# Uno.net
KiCad netlist of a schematic drawn in EAGLE
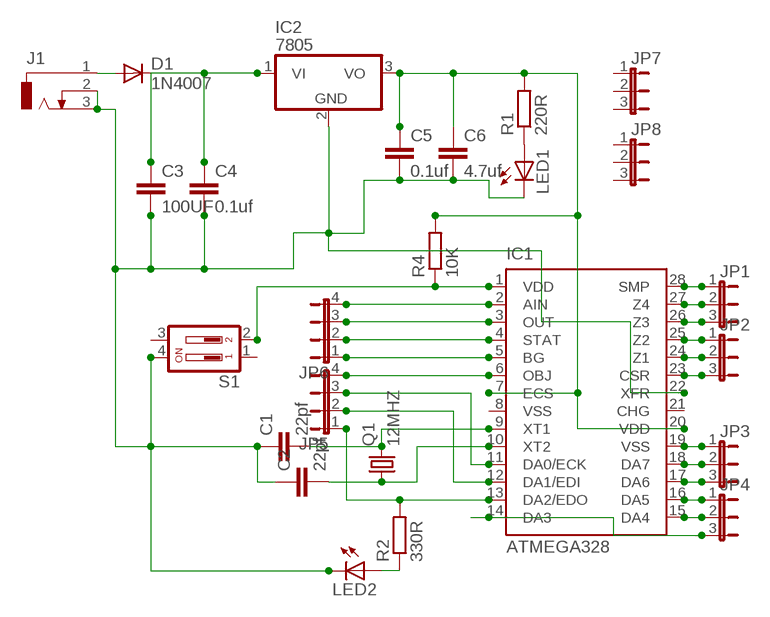
[diagram p0: schematic, sheet 1]

(export (version "E")
  (design (tool "Eeschema 10.0.6"))
  (components
    (comp (ref "C1")
      (value "22pf")
      (footprint "eagle-import:C2.5-2")
      (libsource (lib "eagle-import") (part "C2.5/2"))
    )
    (comp (ref "C2")
      (value "22pf")
      (footprint "eagle-import:C2.5-2")
      (libsource (lib "eagle-import") (part "C2.5/2"))
    )
    (comp (ref "C3")
      (value "100UF")
      (footprint "eagle-import:C2.5-2")
      (libsource (lib "eagle-import") (part "C2.5/2"))
    )
    (comp (ref "C4")
      (value "0.1uf")
      (footprint "eagle-import:C2.5-2")
      (libsource (lib "eagle-import") (part "C2.5/2"))
    )
    (comp (ref "C5")
      (value "0.1uf")
      (footprint "eagle-import:C2.5-2")
      (libsource (lib "eagle-import") (part "C2.5/2"))
    )
    (comp (ref "C6")
      (value "4.7uf")
      (footprint "eagle-import:C2.5-2")
      (libsource (lib "eagle-import") (part "C2.5/2"))
    )
    (comp (ref "D1")
      (value "1N4007")
      (footprint "eagle-import:DO41-10")
      (libsource (lib "eagle-import") (part "1N4004"))
    )
    (comp (ref "IC1")
      (value "ATMEGA328")
      (footprint "eagle-import:DIL28-3")
      (libsource (lib "eagle-import") (part "QT9701BD"))
    )
    (comp (ref "IC2")
      (value "7805")
      (footprint "eagle-import:TO220V")
      (libsource (lib "eagle-import") (part "78TV6"))
    )
    (comp (ref "J1")
      (value "DCJ0303")
      (footprint "eagle-import:DCJ0303")
      (libsource (lib "eagle-import") (part "DCJ0303"))
    )
    (comp (ref "JP1")
      (value "JP2E")
      (footprint "eagle-import:JP2")
      (libsource (lib "eagle-import") (part "JP2E"))
    )
    (comp (ref "JP2")
      (value "JP2E")
      (footprint "eagle-import:JP2")
      (libsource (lib "eagle-import") (part "JP2E"))
    )
    (comp (ref "JP3")
      (value "JP2E")
      (footprint "eagle-import:JP2")
      (libsource (lib "eagle-import") (part "JP2E"))
    )
    (comp (ref "JP4")
      (value "JP2E")
      (footprint "eagle-import:JP2")
      (libsource (lib "eagle-import") (part "JP2E"))
    )
    (comp (ref "JP5")
      (value "JP4E")
      (footprint "eagle-import:JP4")
      (libsource (lib "eagle-import") (part "JP4E"))
    )
    (comp (ref "JP6")
      (value "JP4E")
      (footprint "eagle-import:JP4")
      (libsource (lib "eagle-import") (part "JP4E"))
    )
    (comp (ref "JP7")
      (value "JP2E")
      (footprint "eagle-import:JP2")
      (libsource (lib "eagle-import") (part "JP2E"))
    )
    (comp (ref "JP8")
      (value "JP2E")
      (footprint "eagle-import:JP2")
      (libsource (lib "eagle-import") (part "JP2E"))
    )
    (comp (ref "LED1")
      (value "LED3MM")
      (footprint "eagle-import:LED3MM")
      (libsource (lib "eagle-import") (part "LED3MM"))
    )
    (comp (ref "LED2")
      (value "LED3MM")
      (footprint "eagle-import:LED3MM")
      (libsource (lib "eagle-import") (part "LED3MM"))
    )
    (comp (ref "Q1")
      (value "12MHZ")
      (footprint "eagle-import:HC49_S")
      (libsource (lib "eagle-import") (part "CRYSTALHC49S"))
    )
    (comp (ref "R1")
      (value "220R")
      (footprint "eagle-import:0207_10")
      (libsource (lib "eagle-import") (part "R-EU_0207/10"))
    )
    (comp (ref "R2")
      (value "330R")
      (footprint "eagle-import:0207_10")
      (libsource (lib "eagle-import") (part "R-EU_0207/10"))
    )
    (comp (ref "R4")
      (value "10K")
      (footprint "eagle-import:0207_10")
      (libsource (lib "eagle-import") (part "R-EU_0207/10"))
    )
    (comp (ref "S1")
      (value "DP02")
      (footprint "eagle-import:DP-02")
      (fields (field (name "MPN") "MCDP02"))
      (libsource (lib "eagle-import") (part "DP02"))
    )
  )
  (nets
    (net (code "1") (name "Net-(D1-PadA)") (class "Default")
      (node (ref "D1") (pin "A") (pinfunction "A_A") (pintype "passive"))
      (node (ref "J1") (pin "1") (pinfunction "1_1") (pintype "passive"))
    )
    (net (code "2") (name "Net-(IC1-AIN)") (class "Default")
      (node (ref "IC1") (pin "2") (pinfunction "AIN_2") (pintype "input"))
      (node (ref "JP6") (pin "4") (pinfunction "4_4") (pintype "passive"))
    )
    (net (code "3") (name "Net-(IC1-BG)") (class "Default")
      (node (ref "IC1") (pin "5") (pinfunction "BG_5") (pintype "input"))
      (node (ref "JP6") (pin "1") (pinfunction "1_1") (pintype "passive"))
    )
    (net (code "4") (name "Net-(IC1-CSR)") (class "Default")
      (node (ref "IC1") (pin "23") (pinfunction "CSR_23") (pintype "output"))
      (node (ref "JP2") (pin "3") (pinfunction "3_3") (pintype "passive"))
    )
    (net (code "5") (name "Net-(IC1-DA0{slash}ECK)") (class "Default")
      (node (ref "IC1") (pin "11") (pinfunction "DA0/ECK_11") (pintype "output"))
      (node (ref "JP5") (pin "3") (pinfunction "3_3") (pintype "passive"))
    )
    (net (code "6") (name "Net-(IC1-DA1{slash}EDI)") (class "Default")
      (node (ref "IC1") (pin "12") (pinfunction "DA1/EDI_12") (pintype "output"))
      (node (ref "JP5") (pin "2") (pinfunction "2_2") (pintype "passive"))
    )
    (net (code "7") (name "Net-(IC1-DA2{slash}EDO)") (class "Default")
      (node (ref "IC1") (pin "13") (pinfunction "DA2/EDO_13") (pintype "output"))
      (node (ref "JP5") (pin "1") (pinfunction "1_1") (pintype "passive"))
      (node (ref "R2") (pin "2") (pinfunction "2_2") (pintype "passive"))
    )
    (net (code "8") (name "Net-(IC1-DA3)") (class "Default")
      (node (ref "IC1") (pin "14") (pinfunction "DA3_14") (pintype "output"))
      (node (ref "JP4") (pin "3") (pinfunction "3_3") (pintype "passive"))
    )
    (net (code "9") (name "Net-(IC1-DA4)") (class "Default")
      (node (ref "IC1") (pin "15") (pinfunction "DA4_15") (pintype "output"))
      (node (ref "JP4") (pin "2") (pinfunction "2_2") (pintype "passive"))
    )
    (net (code "10") (name "Net-(IC1-DA5)") (class "Default")
      (node (ref "IC1") (pin "16") (pinfunction "DA5_16") (pintype "output"))
      (node (ref "JP4") (pin "1") (pinfunction "1_1") (pintype "passive"))
    )
    (net (code "11") (name "Net-(IC1-DA6)") (class "Default")
      (node (ref "IC1") (pin "17") (pinfunction "DA6_17") (pintype "output"))
      (node (ref "JP3") (pin "3") (pinfunction "3_3") (pintype "passive"))
    )
    (net (code "12") (name "Net-(IC1-DA7)") (class "Default")
      (node (ref "IC1") (pin "18") (pinfunction "DA7_18") (pintype "output"))
      (node (ref "JP3") (pin "2") (pinfunction "2_2") (pintype "passive"))
    )
    (net (code "13") (name "Net-(IC1-ECS)") (class "Default")
      (node (ref "C5") (pin "1") (pinfunction "1_1") (pintype "passive"))
      (node (ref "C6") (pin "1") (pinfunction "1_1") (pintype "passive"))
      (node (ref "IC1") (pin "20") (pinfunction "VDD_20") (pintype "input"))
      (node (ref "IC1") (pin "7") (pinfunction "ECS_7") (pintype "output"))
      (node (ref "IC2") (pin "3") (pinfunction "VO_3") (pintype "passive"))
      (node (ref "R1") (pin "2") (pinfunction "2_2") (pintype "passive"))
      (node (ref "R4") (pin "2") (pinfunction "2_2") (pintype "passive"))
    )
    (net (code "14") (name "Net-(IC1-OBJ)") (class "Default")
      (node (ref "IC1") (pin "6") (pinfunction "OBJ_6") (pintype "input"))
      (node (ref "JP5") (pin "4") (pinfunction "4_4") (pintype "passive"))
    )
    (net (code "15") (name "Net-(IC1-OUT)") (class "Default")
      (node (ref "IC1") (pin "3") (pinfunction "OUT_3") (pintype "output"))
      (node (ref "JP6") (pin "3") (pinfunction "3_3") (pintype "passive"))
    )
    (net (code "16") (name "Net-(IC1-SMP)") (class "Default")
      (node (ref "IC1") (pin "28") (pinfunction "SMP_28") (pintype "output"))
      (node (ref "JP1") (pin "1") (pinfunction "1_1") (pintype "passive"))
    )
    (net (code "17") (name "Net-(IC1-STAT)") (class "Default")
      (node (ref "IC1") (pin "4") (pinfunction "STAT_4") (pintype "output"))
      (node (ref "JP6") (pin "2") (pinfunction "2_2") (pintype "passive"))
    )
    (net (code "18") (name "Net-(IC1-VDD-Pad1)") (class "Default")
      (node (ref "IC1") (pin "1") (pinfunction "VDD_1") (pintype "input"))
      (node (ref "R4") (pin "1") (pinfunction "1_1") (pintype "passive"))
      (node (ref "S1") (pin "2") (pinfunction "2_2") (pintype "passive"))
    )
    (net (code "19") (name "Net-(IC1-VSS-Pad19)") (class "Default")
      (node (ref "IC1") (pin "19") (pinfunction "VSS_19") (pintype "input"))
      (node (ref "JP3") (pin "1") (pinfunction "1_1") (pintype "passive"))
    )
    (net (code "20") (name "Net-(IC1-XFR)") (class "Default")
      (node (ref "C1") (pin "1") (pinfunction "1_1") (pintype "passive"))
      (node (ref "C2") (pin "1") (pinfunction "1_1") (pintype "passive"))
      (node (ref "C3") (pin "2") (pinfunction "2_2") (pintype "passive"))
      (node (ref "C4") (pin "2") (pinfunction "2_2") (pintype "passive"))
      (node (ref "C5") (pin "2") (pinfunction "2_2") (pintype "passive"))
      (node (ref "C6") (pin "2") (pinfunction "2_2") (pintype "passive"))
      (node (ref "IC1") (pin "22") (pinfunction "XFR_22") (pintype "output"))
      (node (ref "IC2") (pin "2") (pinfunction "GND_2") (pintype "passive"))
      (node (ref "J1") (pin "2") (pinfunction "2_2") (pintype "passive"))
      (node (ref "J1") (pin "3") (pinfunction "3_3") (pintype "passive"))
      (node (ref "LED1") (pin "K") (pinfunction "C_K") (pintype "passive"))
      (node (ref "LED2") (pin "K") (pinfunction "C_K") (pintype "passive"))
      (node (ref "S1") (pin "4") (pinfunction "4_4") (pintype "passive"))
    )
    (net (code "21") (name "Net-(IC1-XT1)") (class "Default")
      (node (ref "C1") (pin "2") (pinfunction "2_2") (pintype "passive"))
      (node (ref "IC1") (pin "9") (pinfunction "XT1_9") (pintype "input"))
      (node (ref "Q1") (pin "2") (pinfunction "2_2") (pintype "passive"))
    )
    (net (code "22") (name "Net-(IC1-XT2)") (class "Default")
      (node (ref "C2") (pin "2") (pinfunction "2_2") (pintype "passive"))
      (node (ref "IC1") (pin "10") (pinfunction "XT2_10") (pintype "output"))
      (node (ref "Q1") (pin "1") (pinfunction "1_1") (pintype "passive"))
    )
    (net (code "23") (name "Net-(IC1-Z1)") (class "Default")
      (node (ref "IC1") (pin "24") (pinfunction "Z1_24") (pintype "output"))
      (node (ref "JP2") (pin "2") (pinfunction "2_2") (pintype "passive"))
    )
    (net (code "24") (name "Net-(IC1-Z2)") (class "Default")
      (node (ref "IC1") (pin "25") (pinfunction "Z2_25") (pintype "output"))
      (node (ref "JP2") (pin "1") (pinfunction "1_1") (pintype "passive"))
    )
    (net (code "25") (name "Net-(IC1-Z3)") (class "Default")
      (node (ref "IC1") (pin "26") (pinfunction "Z3_26") (pintype "output"))
      (node (ref "JP1") (pin "3") (pinfunction "3_3") (pintype "passive"))
    )
    (net (code "26") (name "Net-(IC1-Z4)") (class "Default")
      (node (ref "IC1") (pin "27") (pinfunction "Z4_27") (pintype "output"))
      (node (ref "JP1") (pin "2") (pinfunction "2_2") (pintype "passive"))
    )
    (net (code "27") (name "Net-(IC2-VI)") (class "Default")
      (node (ref "C3") (pin "1") (pinfunction "1_1") (pintype "passive"))
      (node (ref "C4") (pin "1") (pinfunction "1_1") (pintype "passive"))
      (node (ref "D1") (pin "C") (pinfunction "C_C") (pintype "passive"))
      (node (ref "IC2") (pin "1") (pinfunction "VI_1") (pintype "input"))
    )
    (net (code "28") (name "Net-(LED1-PadA)") (class "Default")
      (node (ref "LED1") (pin "A") (pinfunction "A_A") (pintype "passive"))
      (node (ref "R1") (pin "1") (pinfunction "1_1") (pintype "passive"))
    )
    (net (code "29") (name "Net-(LED2-PadA)") (class "Default")
      (node (ref "LED2") (pin "A") (pinfunction "A_A") (pintype "passive"))
      (node (ref "R2") (pin "1") (pinfunction "1_1") (pintype "passive"))
    )
    (net (code "30") (name "unconnected-(IC1-CHG-Pad21)") (class "Default")
      (node (ref "IC1") (pin "21") (pinfunction "CHG_21") (pintype "output"))
    )
    (net (code "31") (name "unconnected-(IC1-VSS-Pad8)") (class "Default")
      (node (ref "IC1") (pin "8") (pinfunction "VSS_8") (pintype "input"))
    )
    (net (code "32") (name "unconnected-(JP7-Pad1)") (class "Default")
      (node (ref "JP7") (pin "1") (pinfunction "1_1") (pintype "passive"))
    )
    (net (code "33") (name "unconnected-(JP7-Pad2)") (class "Default")
      (node (ref "JP7") (pin "2") (pinfunction "2_2") (pintype "passive"))
    )
    (net (code "34") (name "unconnected-(JP7-Pad3)") (class "Default")
      (node (ref "JP7") (pin "3") (pinfunction "3_3") (pintype "passive"))
    )
    (net (code "35") (name "unconnected-(JP8-Pad1)") (class "Default")
      (node (ref "JP8") (pin "1") (pinfunction "1_1") (pintype "passive"))
    )
    (net (code "36") (name "unconnected-(JP8-Pad2)") (class "Default")
      (node (ref "JP8") (pin "2") (pinfunction "2_2") (pintype "passive"))
    )
    (net (code "37") (name "unconnected-(JP8-Pad3)") (class "Default")
      (node (ref "JP8") (pin "3") (pinfunction "3_3") (pintype "passive"))
    )
    (net (code "38") (name "unconnected-(S1-Pad1)") (class "Default")
      (node (ref "S1") (pin "1") (pinfunction "1_1") (pintype "passive"))
    )
    (net (code "39") (name "unconnected-(S1-Pad3)") (class "Default")
      (node (ref "S1") (pin "3") (pinfunction "3_3") (pintype "passive"))
    )
  )
)
